# Turntable.net
KiCad netlist of a schematic drawn in EAGLE
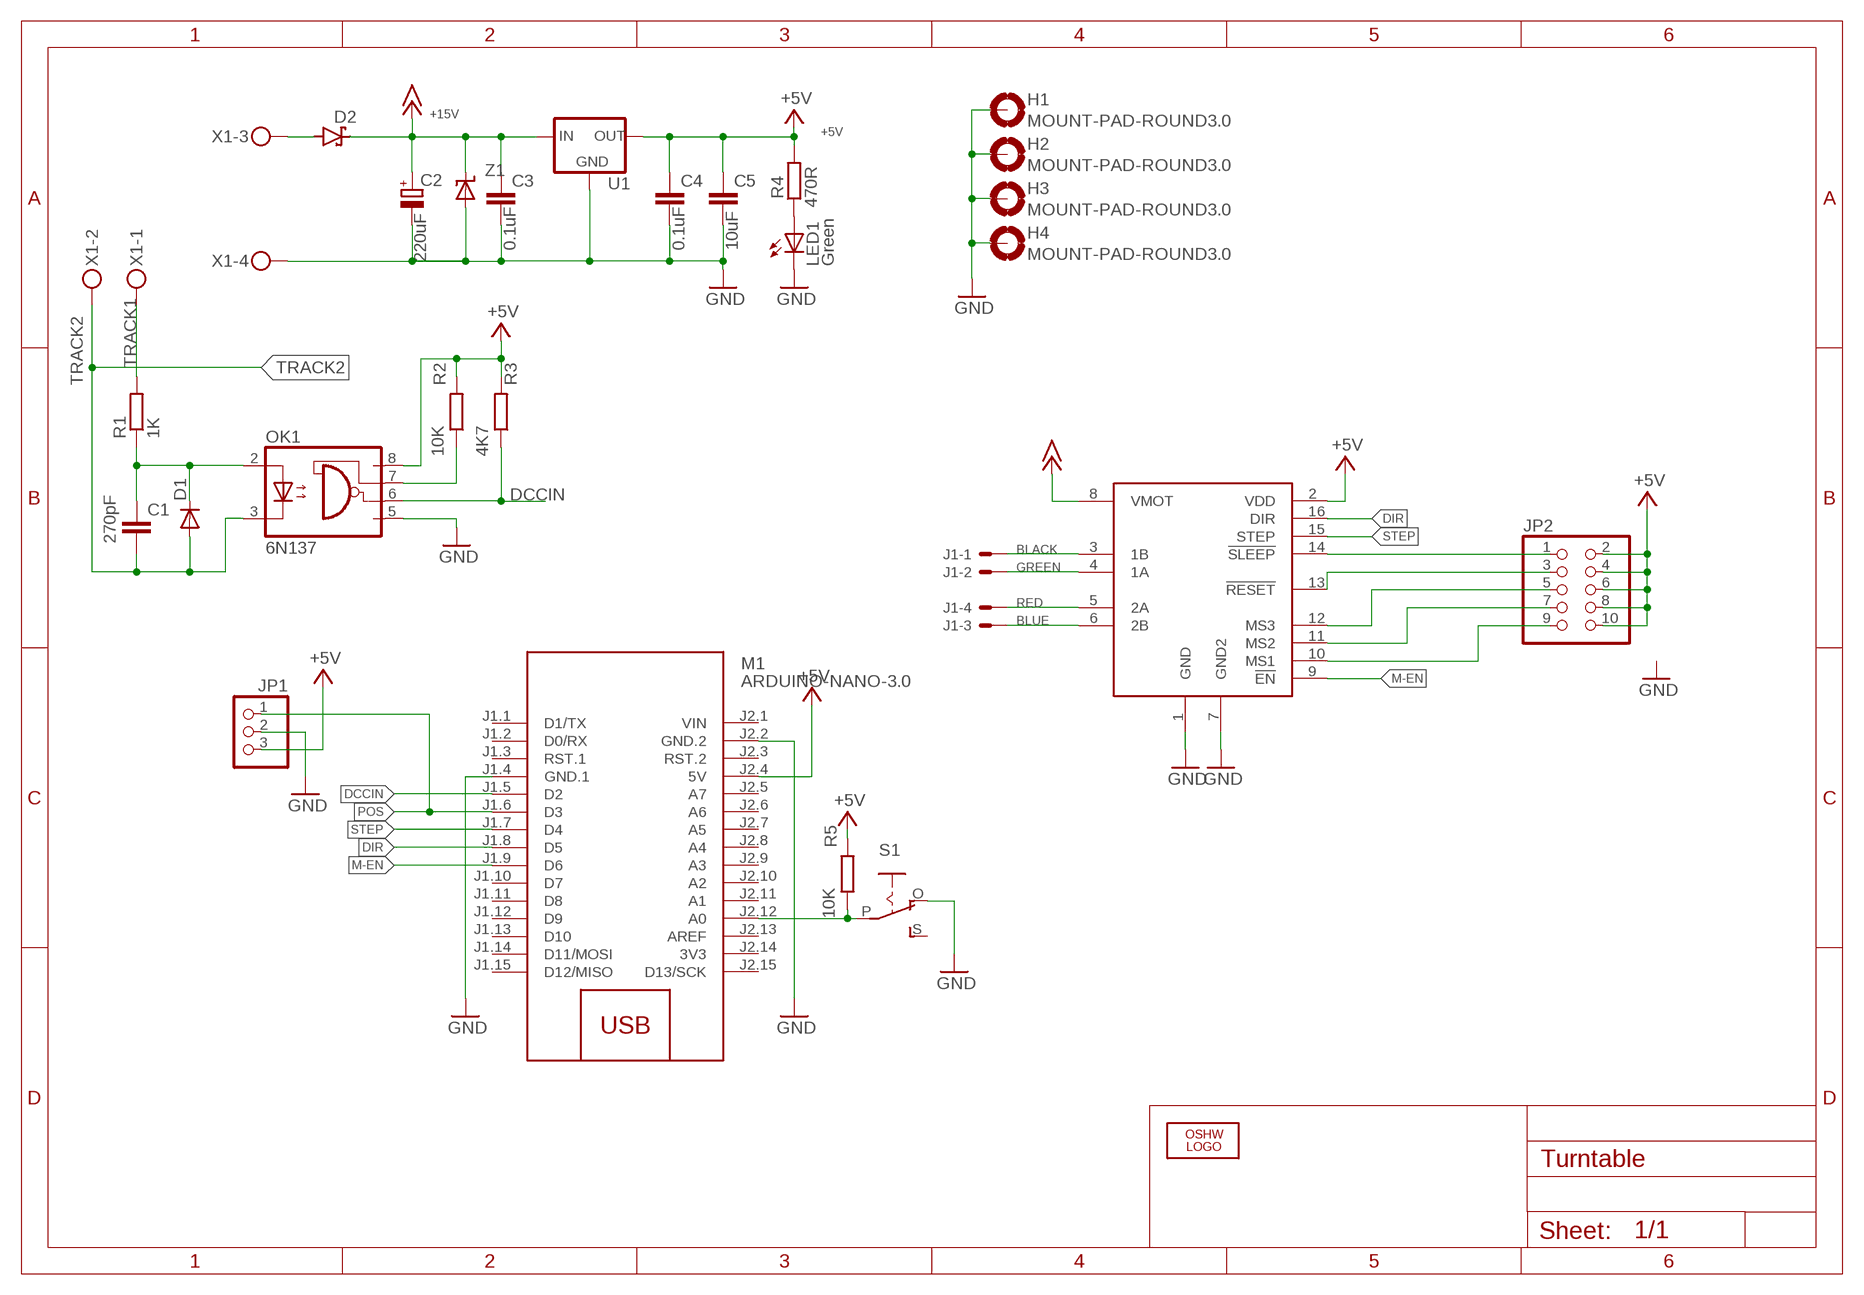
[diagram p0: schematic, sheet 1]

(export (version "E")
  (design (tool "Eeschema 10.0.6"))
  (components
    (comp (ref "C1")
      (value "270pF")
      (footprint "eagle-import:C0805")
      (libsource (lib "eagle-import") (part "C-EUC0805"))
    )
    (comp (ref "C2")
      (value "220uF")
      (footprint "eagle-import:E7,5-16")
      (libsource (lib "eagle-import") (part "CPOL-EUE7.5-16"))
    )
    (comp (ref "C3")
      (value "0.1uF")
      (footprint "eagle-import:C0805")
      (libsource (lib "eagle-import") (part "C-EUC0805"))
    )
    (comp (ref "C4")
      (value "0.1uF")
      (footprint "eagle-import:C0805")
      (libsource (lib "eagle-import") (part "C-EUC0805"))
    )
    (comp (ref "C5")
      (value "10uF")
      (footprint "eagle-import:C0805")
      (libsource (lib "eagle-import") (part "C-EUC0805"))
    )
    (comp (ref "D1")
      (value "CGRM4002-G")
      (footprint "eagle-import:SOD-123_MINI-SMA")
      (libsource (lib "eagle-import") (part "CGRM400-G2"))
    )
    (comp (ref "D2")
      (value "SCHOTTKY-DIODESMD")
      (footprint "eagle-import:SMB")
      (libsource (lib "eagle-import") (part "SCHOTTKY-DIODESMD"))
    )
    (comp (ref "H1")
      (value "MOUNT-PAD-ROUND3.0")
      (footprint "eagle-import:3,0-PAD")
      (libsource (lib "eagle-import") (part "MOUNT-PAD-ROUND3.0"))
    )
    (comp (ref "H2")
      (value "MOUNT-PAD-ROUND3.0")
      (footprint "eagle-import:3,0-PAD")
      (libsource (lib "eagle-import") (part "MOUNT-PAD-ROUND3.0"))
    )
    (comp (ref "H3")
      (value "MOUNT-PAD-ROUND3.0")
      (footprint "eagle-import:3,0-PAD")
      (libsource (lib "eagle-import") (part "MOUNT-PAD-ROUND3.0"))
    )
    (comp (ref "H4")
      (value "MOUNT-PAD-ROUND3.0")
      (footprint "eagle-import:3,0-PAD")
      (libsource (lib "eagle-import") (part "MOUNT-PAD-ROUND3.0"))
    )
    (comp (ref "J1")
      (value "HEADER4")
      (footprint "eagle-import:HEADER4")
      (libsource (lib "eagle-import") (part "HEADER4"))
    )
    (comp (ref "JP1")
      (value "PINHD-1X3")
      (footprint "eagle-import:1X03")
      (libsource (lib "eagle-import") (part "PINHD-1X3"))
    )
    (comp (ref "JP2")
      (value "PINHD-2X5")
      (footprint "eagle-import:2X05")
      (libsource (lib "eagle-import") (part "PINHD-2X5"))
    )
    (comp (ref "LED1")
      (value "Green")
      (footprint "eagle-import:LED3MM")
      (libsource (lib "eagle-import") (part "LED3MM"))
    )
    (comp (ref "LOGO1")
      (value "OSHW_LOGO_6MILX0200-NT")
      (footprint "eagle-import:OSHW_6X200_NOTEXT")
      (libsource (lib "eagle-import") (part "OSHW_LOGO_6MILX0200-NT"))
    )
    (comp (ref "M1")
      (value "ARDUINO-NANO-3.0")
      (footprint "eagle-import:ARDUINO-NANO-3.0")
      (libsource (lib "eagle-import") (part "ARDUINO-NANO-3.0"))
    )
    (comp (ref "OK1")
      (value "6N137")
      (footprint "eagle-import:DIL08")
      (libsource (lib "eagle-import") (part "6N137"))
    )
    (comp (ref "R1")
      (value "1K")
      (footprint "eagle-import:R0805")
      (libsource (lib "eagle-import") (part "R-EU_R0805"))
    )
    (comp (ref "R2")
      (value "10K")
      (footprint "eagle-import:R0805")
      (libsource (lib "eagle-import") (part "R-EU_R0805"))
    )
    (comp (ref "R3")
      (value "4K7")
      (footprint "eagle-import:R0805")
      (libsource (lib "eagle-import") (part "R-EU_R0805"))
    )
    (comp (ref "R4")
      (value "470R")
      (footprint "eagle-import:R0805")
      (libsource (lib "eagle-import") (part "R-EU_R0805"))
    )
    (comp (ref "R5")
      (value "10K")
      (footprint "eagle-import:R0805")
      (libsource (lib "eagle-import") (part "R-EU_R0805"))
    )
    (comp (ref "S1")
      (value "EG1218S")
      (footprint "eagle-import:EG1218")
      (libsource (lib "eagle-import") (part "EG1218S"))
    )
    (comp (ref "U1")
      (value "V_REG_78XX-TO-220")
      (footprint "eagle-import:TO-220-ALT")
      (libsource (lib "eagle-import") (part "V_REG_78XX-TO-220"))
    )
    (comp (ref "U2")
      (value "A4988")
      (footprint "eagle-import:POLOLUA4988")
      (libsource (lib "eagle-import") (part "A4988"))
    )
    (comp (ref "X1")
      (value "MKDSN1,5/4-5,08")
      (footprint "eagle-import:MKDSN1,5_4-5,08")
      (fields (field (name "MPN") "SMKDSN1,5/4-5,08"))
      (libsource (lib "eagle-import") (part "MKDSN1,5/4-5,08"))
    )
    (comp (ref "Z1")
      (value "TRANSZORB")
      (footprint "eagle-import:SMB")
      (fields (field (name "VOLTAGE") "15V"))
      (libsource (lib "eagle-import") (part "TRANSZORB"))
    )
  )
  (nets
    (net (code "1") (name "+5V") (class "Default")
      (node (ref "C4") (pin "1") (pinfunction "1_1") (pintype "passive"))
      (node (ref "C5") (pin "1") (pinfunction "1_1") (pintype "passive"))
      (node (ref "JP1") (pin "3") (pinfunction "3_3") (pintype "passive"))
      (node (ref "JP2") (pin "10") (pinfunction "10_10") (pintype "passive"))
      (node (ref "JP2") (pin "2") (pinfunction "2_2") (pintype "passive"))
      (node (ref "JP2") (pin "4") (pinfunction "4_4") (pintype "passive"))
      (node (ref "JP2") (pin "6") (pinfunction "6_6") (pintype "passive"))
      (node (ref "JP2") (pin "8") (pinfunction "8_8") (pintype "passive"))
      (node (ref "M1") (pin "J2.4") (pinfunction "5V_J2.4") (pintype "power_in"))
      (node (ref "OK1") (pin "8") (pinfunction "VCC_8") (pintype "passive"))
      (node (ref "R2") (pin "2") (pinfunction "2_2") (pintype "passive"))
      (node (ref "R3") (pin "2") (pinfunction "2_2") (pintype "passive"))
      (node (ref "R4") (pin "2") (pinfunction "2_2") (pintype "passive"))
      (node (ref "R5") (pin "2") (pinfunction "2_2") (pintype "passive"))
      (node (ref "U1") (pin "OUT") (pinfunction "OUT_OUT") (pintype "passive"))
      (node (ref "U2") (pin "2") (pinfunction "VDD_2") (pintype "power_in"))
    )
    (net (code "2") (name "+15V") (class "Default")
      (node (ref "C2") (pin "+") (pinfunction "+_+") (pintype "passive"))
      (node (ref "C3") (pin "1") (pinfunction "1_1") (pintype "passive"))
      (node (ref "D2") (pin "C") (pinfunction "C_C") (pintype "passive"))
      (node (ref "U1") (pin "IN") (pinfunction "IN_IN") (pintype "input"))
      (node (ref "U2") (pin "8") (pinfunction "VMOT_8") (pintype "bidirectional"))
      (node (ref "Z1") (pin "1") (pinfunction "C_1") (pintype "passive"))
    )
    (net (code "3") (name "/3V3") (class "Default")
      (node (ref "M1") (pin "J2.14") (pinfunction "3V3_J2.14") (pintype "power_in"))
    )
    (net (code "4") (name "/BLACK") (class "Default")
      (node (ref "J1") (pin "1") (pinfunction "S_1") (pintype "passive"))
      (node (ref "U2") (pin "3") (pinfunction "1B_3") (pintype "open_collector"))
    )
    (net (code "5") (name "/BLUE") (class "Default")
      (node (ref "J1") (pin "3") (pinfunction "S_3") (pintype "passive"))
      (node (ref "U2") (pin "6") (pinfunction "2B_6") (pintype "open_collector"))
    )
    (net (code "6") (name "/GREEN") (class "Default")
      (node (ref "J1") (pin "2") (pinfunction "S_2") (pintype "passive"))
      (node (ref "U2") (pin "4") (pinfunction "1A_4") (pintype "open_collector"))
    )
    (net (code "7") (name "/RED") (class "Default")
      (node (ref "J1") (pin "4") (pinfunction "S_4") (pintype "passive"))
      (node (ref "U2") (pin "5") (pinfunction "2A_5") (pintype "open_collector"))
    )
    (net (code "8") (name "/TRACK1") (class "Default")
      (node (ref "R1") (pin "2") (pinfunction "2_2") (pintype "passive"))
      (node (ref "X1") (pin "1") (pinfunction "KL_1") (pintype "passive"))
    )
    (net (code "9") (name "/VIN") (class "Default")
      (node (ref "M1") (pin "J2.1") (pinfunction "VIN_J2.1") (pintype "power_in"))
    )
    (net (code "10") (name "DCCIN") (class "Default")
      (node (ref "M1") (pin "J1.5") (pinfunction "D2_J1.5") (pintype "bidirectional"))
      (node (ref "OK1") (pin "6") (pinfunction "VO_6") (pintype "passive"))
      (node (ref "R3") (pin "1") (pinfunction "1_1") (pintype "passive"))
    )
    (net (code "11") (name "DIR") (class "Default")
      (node (ref "M1") (pin "J1.8") (pinfunction "D5_J1.8") (pintype "bidirectional"))
      (node (ref "U2") (pin "16") (pinfunction "DIR_16") (pintype "input"))
    )
    (net (code "12") (name "GND") (class "Default")
      (node (ref "C2") (pin "-") (pinfunction "-_-") (pintype "passive"))
      (node (ref "C3") (pin "2") (pinfunction "2_2") (pintype "passive"))
      (node (ref "C4") (pin "2") (pinfunction "2_2") (pintype "passive"))
      (node (ref "C5") (pin "2") (pinfunction "2_2") (pintype "passive"))
      (node (ref "H1") (pin "B3,0") (pinfunction "MOUNT_B3,0") (pintype "passive"))
      (node (ref "H2") (pin "B3,0") (pinfunction "MOUNT_B3,0") (pintype "passive"))
      (node (ref "H3") (pin "B3,0") (pinfunction "MOUNT_B3,0") (pintype "passive"))
      (node (ref "H4") (pin "B3,0") (pinfunction "MOUNT_B3,0") (pintype "passive"))
      (node (ref "JP1") (pin "2") (pinfunction "2_2") (pintype "passive"))
      (node (ref "LED1") (pin "K") (pinfunction "C_K") (pintype "passive"))
      (node (ref "M1") (pin "J1.4") (pinfunction "GND.1_J1.4") (pintype "power_in"))
      (node (ref "M1") (pin "J2.2") (pinfunction "GND.2_J2.2") (pintype "power_in"))
      (node (ref "OK1") (pin "5") (pinfunction "GND_5") (pintype "passive"))
      (node (ref "S1") (pin "O") (pinfunction "O_O") (pintype "passive"))
      (node (ref "U1") (pin "GND") (pinfunction "GND_GND") (pintype "input"))
      (node (ref "U2") (pin "1") (pinfunction "GND_1") (pintype "passive"))
      (node (ref "U2") (pin "7") (pinfunction "GND2_7") (pintype "bidirectional"))
      (node (ref "X1") (pin "4") (pinfunction "KL_4") (pintype "passive"))
      (node (ref "Z1") (pin "2") (pinfunction "A_2") (pintype "passive"))
    )
    (net (code "13") (name "M-EN") (class "Default")
      (node (ref "M1") (pin "J1.9") (pinfunction "D6_J1.9") (pintype "bidirectional"))
      (node (ref "U2") (pin "9") (pinfunction "~{EN}_9") (pintype "input"))
    )
    (net (code "14") (name "Net-(LED1-PadA)") (class "Default")
      (node (ref "LED1") (pin "A") (pinfunction "A_A") (pintype "passive"))
      (node (ref "R4") (pin "1") (pinfunction "1_1") (pintype "passive"))
    )
    (net (code "15") (name "Net-(M1-A0)") (class "Default")
      (node (ref "M1") (pin "J2.12") (pinfunction "A0_J2.12") (pintype "bidirectional"))
      (node (ref "R5") (pin "1") (pinfunction "1_1") (pintype "passive"))
      (node (ref "S1") (pin "P") (pinfunction "P_P") (pintype "passive"))
    )
    (net (code "16") (name "Net-(OK1-A)") (class "Default")
      (node (ref "C1") (pin "1") (pinfunction "1_1") (pintype "passive"))
      (node (ref "D1") (pin "C") (pinfunction "C_C") (pintype "passive"))
      (node (ref "OK1") (pin "2") (pinfunction "A_2") (pintype "passive"))
      (node (ref "R1") (pin "1") (pinfunction "1_1") (pintype "passive"))
    )
    (net (code "17") (name "Net-(OK1-VE)") (class "Default")
      (node (ref "OK1") (pin "7") (pinfunction "VE_7") (pintype "passive"))
      (node (ref "R2") (pin "1") (pinfunction "1_1") (pintype "passive"))
    )
    (net (code "18") (name "Net-(U2-MS1)") (class "Default")
      (node (ref "JP2") (pin "9") (pinfunction "9_9") (pintype "passive"))
      (node (ref "U2") (pin "10") (pinfunction "MS1_10") (pintype "input"))
    )
    (net (code "19") (name "Net-(U2-MS2)") (class "Default")
      (node (ref "JP2") (pin "7") (pinfunction "7_7") (pintype "passive"))
      (node (ref "U2") (pin "11") (pinfunction "MS2_11") (pintype "input"))
    )
    (net (code "20") (name "Net-(U2-MS3)") (class "Default")
      (node (ref "JP2") (pin "5") (pinfunction "5_5") (pintype "passive"))
      (node (ref "U2") (pin "12") (pinfunction "MS3_12") (pintype "input"))
    )
    (net (code "21") (name "Net-(U2-~{RESET})") (class "Default")
      (node (ref "JP2") (pin "3") (pinfunction "3_3") (pintype "passive"))
      (node (ref "U2") (pin "13") (pinfunction "~{RESET}_13") (pintype "input"))
    )
    (net (code "22") (name "Net-(U2-~{SLEEP})") (class "Default")
      (node (ref "JP2") (pin "1") (pinfunction "1_1") (pintype "passive"))
      (node (ref "U2") (pin "14") (pinfunction "~{SLEEP}_14") (pintype "input"))
    )
    (net (code "23") (name "Net-(X1C-KL)") (class "Default")
      (node (ref "D2") (pin "A") (pinfunction "A_A") (pintype "passive"))
      (node (ref "X1") (pin "3") (pinfunction "KL_3") (pintype "passive"))
    )
    (net (code "24") (name "POS") (class "Default")
      (node (ref "JP1") (pin "1") (pinfunction "1_1") (pintype "passive"))
      (node (ref "M1") (pin "J1.6") (pinfunction "D3_J1.6") (pintype "bidirectional"))
    )
    (net (code "25") (name "STEP") (class "Default")
      (node (ref "M1") (pin "J1.7") (pinfunction "D4_J1.7") (pintype "bidirectional"))
      (node (ref "U2") (pin "15") (pinfunction "STEP_15") (pintype "input"))
    )
    (net (code "26") (name "TRACK2") (class "Default")
      (node (ref "C1") (pin "2") (pinfunction "2_2") (pintype "passive"))
      (node (ref "D1") (pin "A") (pinfunction "A_A") (pintype "passive"))
      (node (ref "OK1") (pin "3") (pinfunction "C_3") (pintype "passive"))
      (node (ref "X1") (pin "2") (pinfunction "KL_2") (pintype "passive"))
    )
    (net (code "27") (name "unconnected-(M1-A1-PadJ2.11)") (class "Default")
      (node (ref "M1") (pin "J2.11") (pinfunction "A1_J2.11") (pintype "bidirectional"))
    )
    (net (code "28") (name "unconnected-(M1-A2-PadJ2.10)") (class "Default")
      (node (ref "M1") (pin "J2.10") (pinfunction "A2_J2.10") (pintype "bidirectional"))
    )
    (net (code "29") (name "unconnected-(M1-A3-PadJ2.9)") (class "Default")
      (node (ref "M1") (pin "J2.9") (pinfunction "A3_J2.9") (pintype "bidirectional"))
    )
    (net (code "30") (name "unconnected-(M1-A4-PadJ2.8)") (class "Default")
      (node (ref "M1") (pin "J2.8") (pinfunction "A4_J2.8") (pintype "bidirectional"))
    )
    (net (code "31") (name "unconnected-(M1-A5-PadJ2.7)") (class "Default")
      (node (ref "M1") (pin "J2.7") (pinfunction "A5_J2.7") (pintype "bidirectional"))
    )
    (net (code "32") (name "unconnected-(M1-A6-PadJ2.6)") (class "Default")
      (node (ref "M1") (pin "J2.6") (pinfunction "A6_J2.6") (pintype "bidirectional"))
    )
    (net (code "33") (name "unconnected-(M1-A7-PadJ2.5)") (class "Default")
      (node (ref "M1") (pin "J2.5") (pinfunction "A7_J2.5") (pintype "bidirectional"))
    )
    (net (code "34") (name "unconnected-(M1-AREF-PadJ2.13)") (class "Default")
      (node (ref "M1") (pin "J2.13") (pinfunction "AREF_J2.13") (pintype "bidirectional"))
    )
    (net (code "35") (name "unconnected-(M1-D0{slash}RX-PadJ1.2)") (class "Default")
      (node (ref "M1") (pin "J1.2") (pinfunction "D0/RX_J1.2") (pintype "bidirectional"))
    )
    (net (code "36") (name "unconnected-(M1-D1{slash}TX-PadJ1.1)") (class "Default")
      (node (ref "M1") (pin "J1.1") (pinfunction "D1/TX_J1.1") (pintype "bidirectional"))
    )
    (net (code "37") (name "unconnected-(M1-D7-PadJ1.10)") (class "Default")
      (node (ref "M1") (pin "J1.10") (pinfunction "D7_J1.10") (pintype "bidirectional"))
    )
    (net (code "38") (name "unconnected-(M1-D8-PadJ1.11)") (class "Default")
      (node (ref "M1") (pin "J1.11") (pinfunction "D8_J1.11") (pintype "bidirectional"))
    )
    (net (code "39") (name "unconnected-(M1-D9-PadJ1.12)") (class "Default")
      (node (ref "M1") (pin "J1.12") (pinfunction "D9_J1.12") (pintype "bidirectional"))
    )
    (net (code "40") (name "unconnected-(M1-D10-PadJ1.13)") (class "Default")
      (node (ref "M1") (pin "J1.13") (pinfunction "D10_J1.13") (pintype "bidirectional"))
    )
    (net (code "41") (name "unconnected-(M1-D11{slash}MOSI-PadJ1.14)") (class "Default")
      (node (ref "M1") (pin "J1.14") (pinfunction "D11/MOSI_J1.14") (pintype "bidirectional"))
    )
    (net (code "42") (name "unconnected-(M1-D12{slash}MISO-PadJ1.15)") (class "Default")
      (node (ref "M1") (pin "J1.15") (pinfunction "D12/MISO_J1.15") (pintype "bidirectional"))
    )
    (net (code "43") (name "unconnected-(M1-D13{slash}SCK-PadJ2.15)") (class "Default")
      (node (ref "M1") (pin "J2.15") (pinfunction "D13/SCK_J2.15") (pintype "bidirectional"))
    )
    (net (code "44") (name "unconnected-(M1-RST.1-PadJ1.3)") (class "Default")
      (node (ref "M1") (pin "J1.3") (pinfunction "RST.1_J1.3") (pintype "bidirectional"))
    )
    (net (code "45") (name "unconnected-(M1-RST.2-PadJ2.3)") (class "Default")
      (node (ref "M1") (pin "J2.3") (pinfunction "RST.2_J2.3") (pintype "bidirectional"))
    )
    (net (code "46") (name "unconnected-(S1-PadS)") (class "Default")
      (node (ref "S1") (pin "S") (pinfunction "S_S") (pintype "passive"))
    )
  )
)
